# E-P-206-R1_0_Fuel_Cell_Control.net
KiCad netlist of a schematic drawn in EAGLE
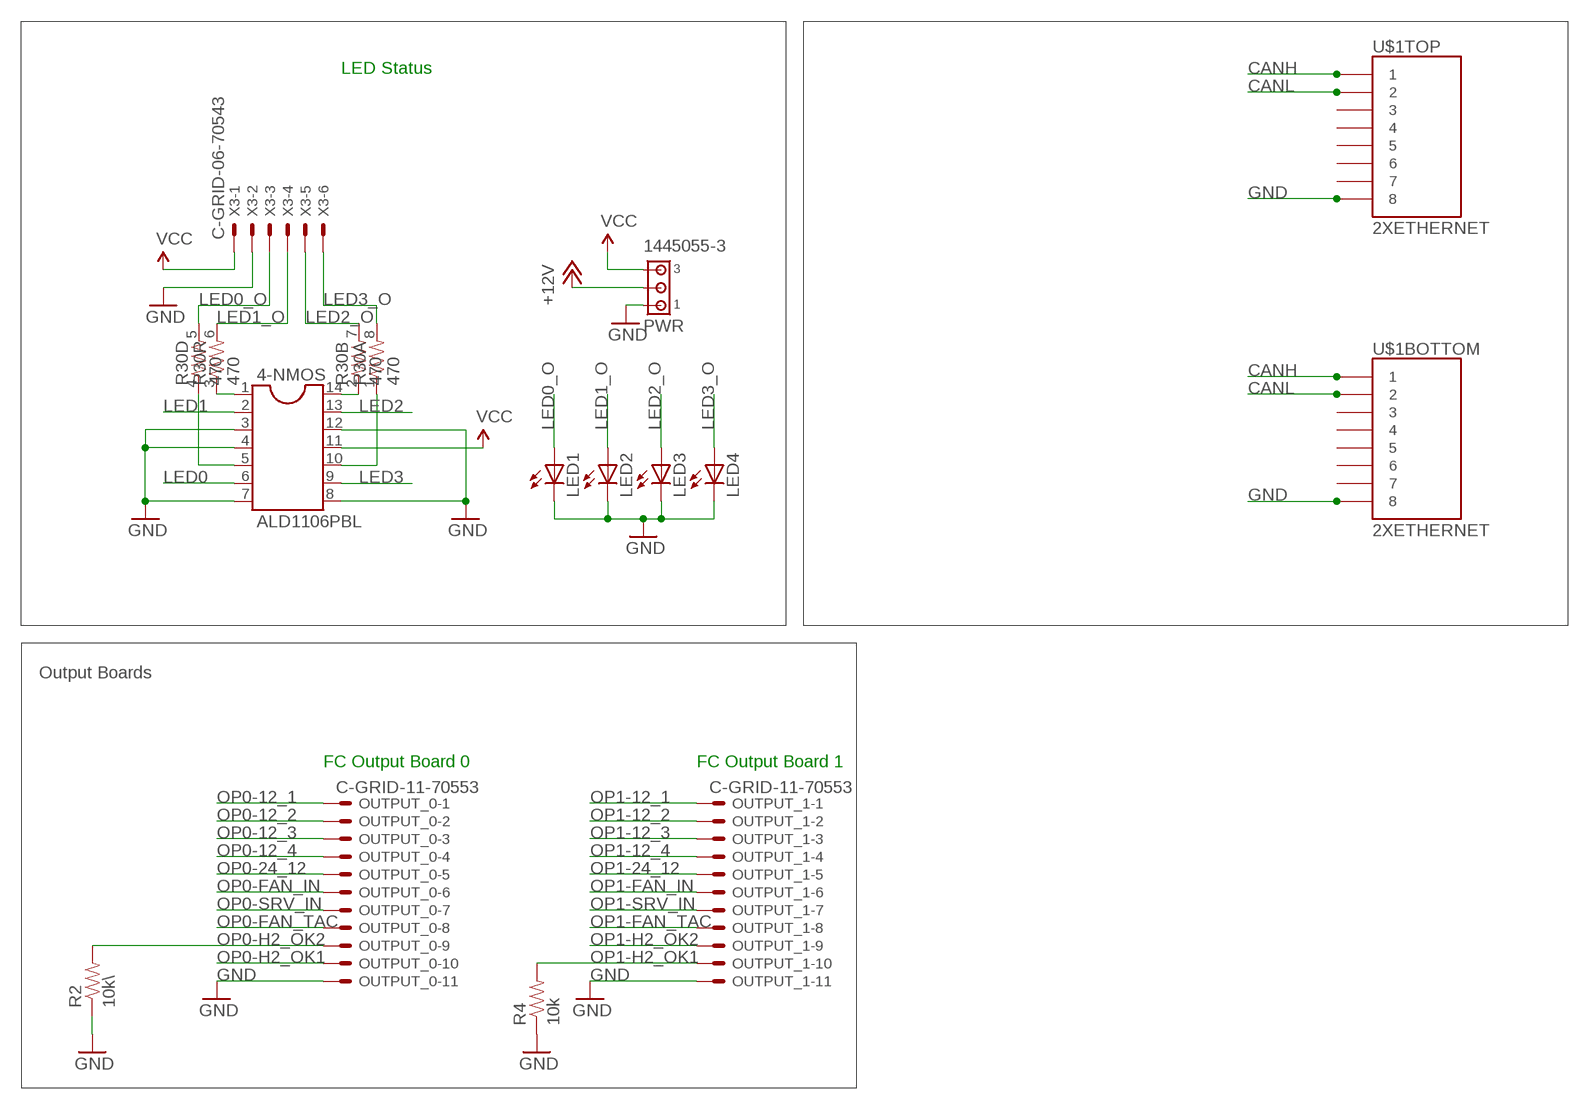
[diagram p0: schematic, sheet 1]
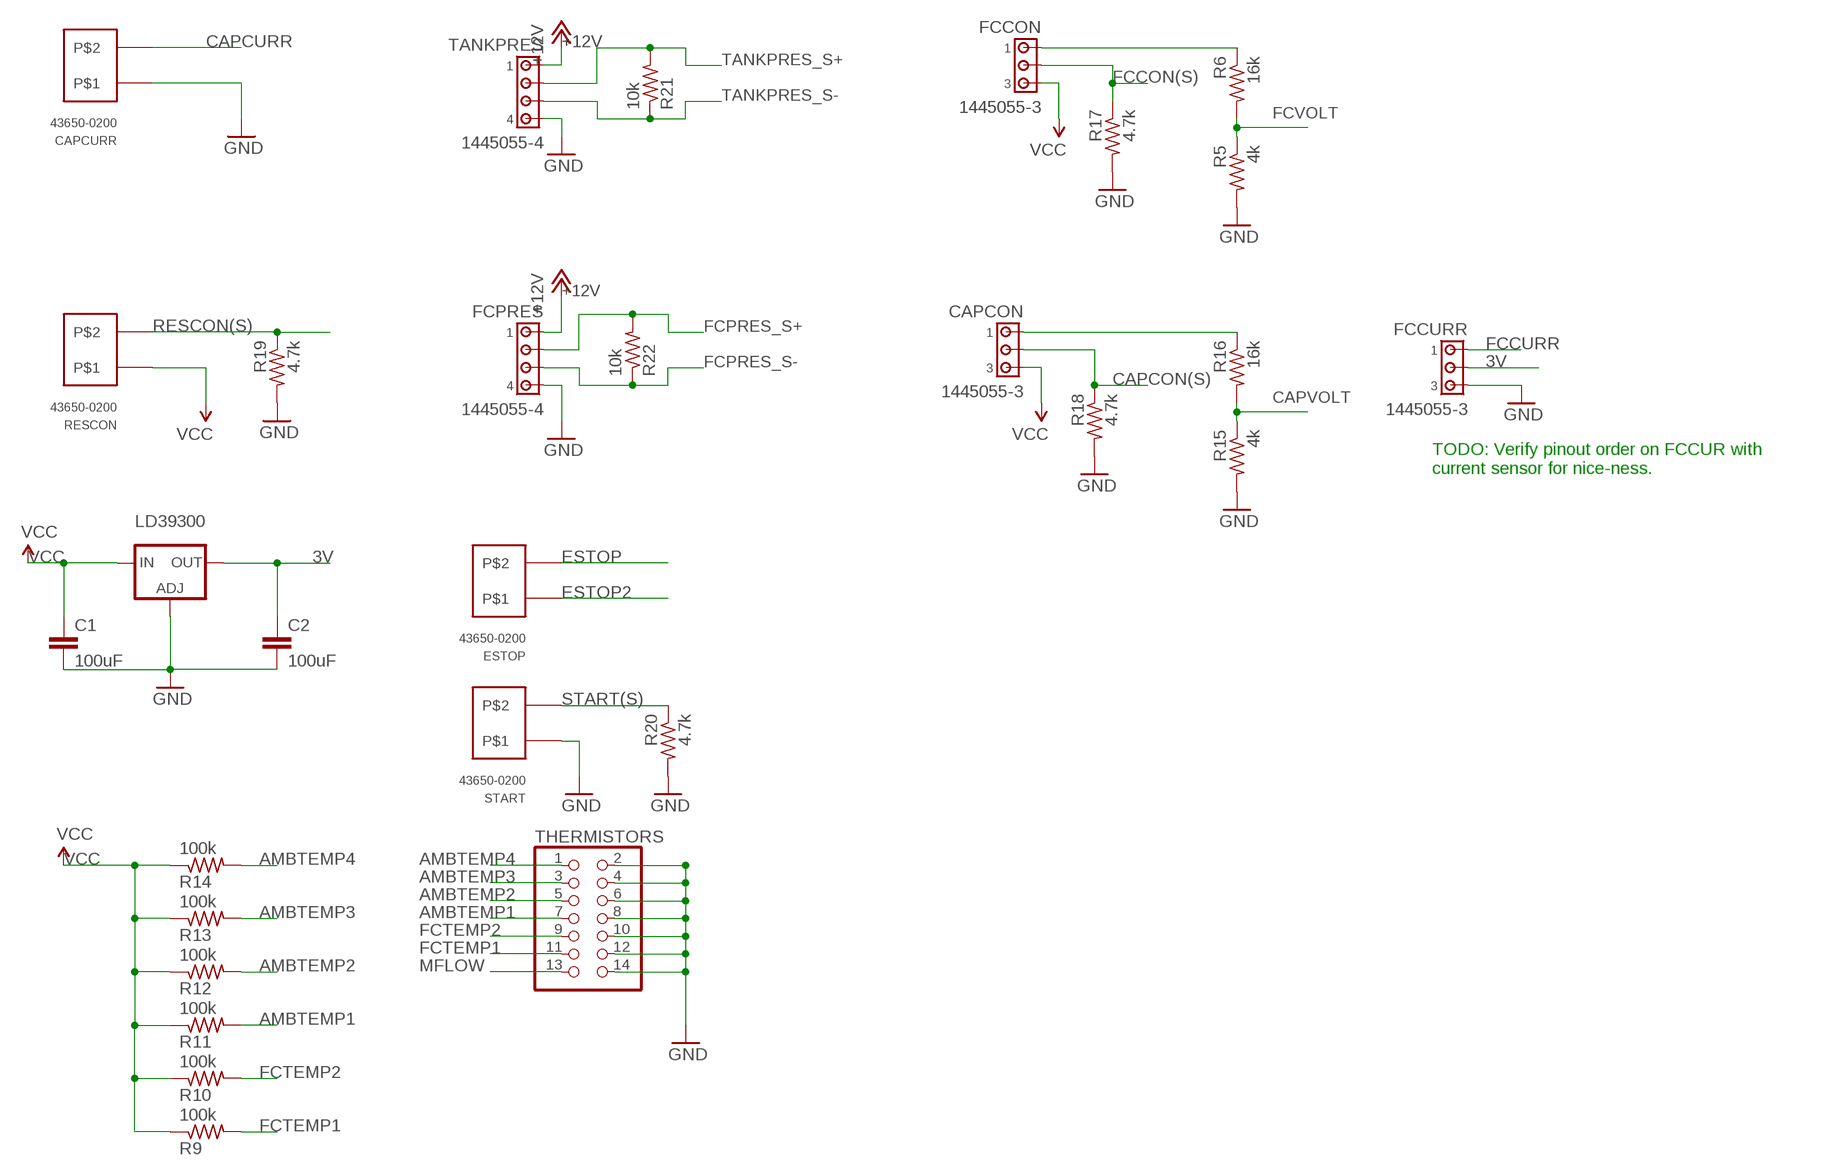
[diagram p1: schematic, sheet 2]
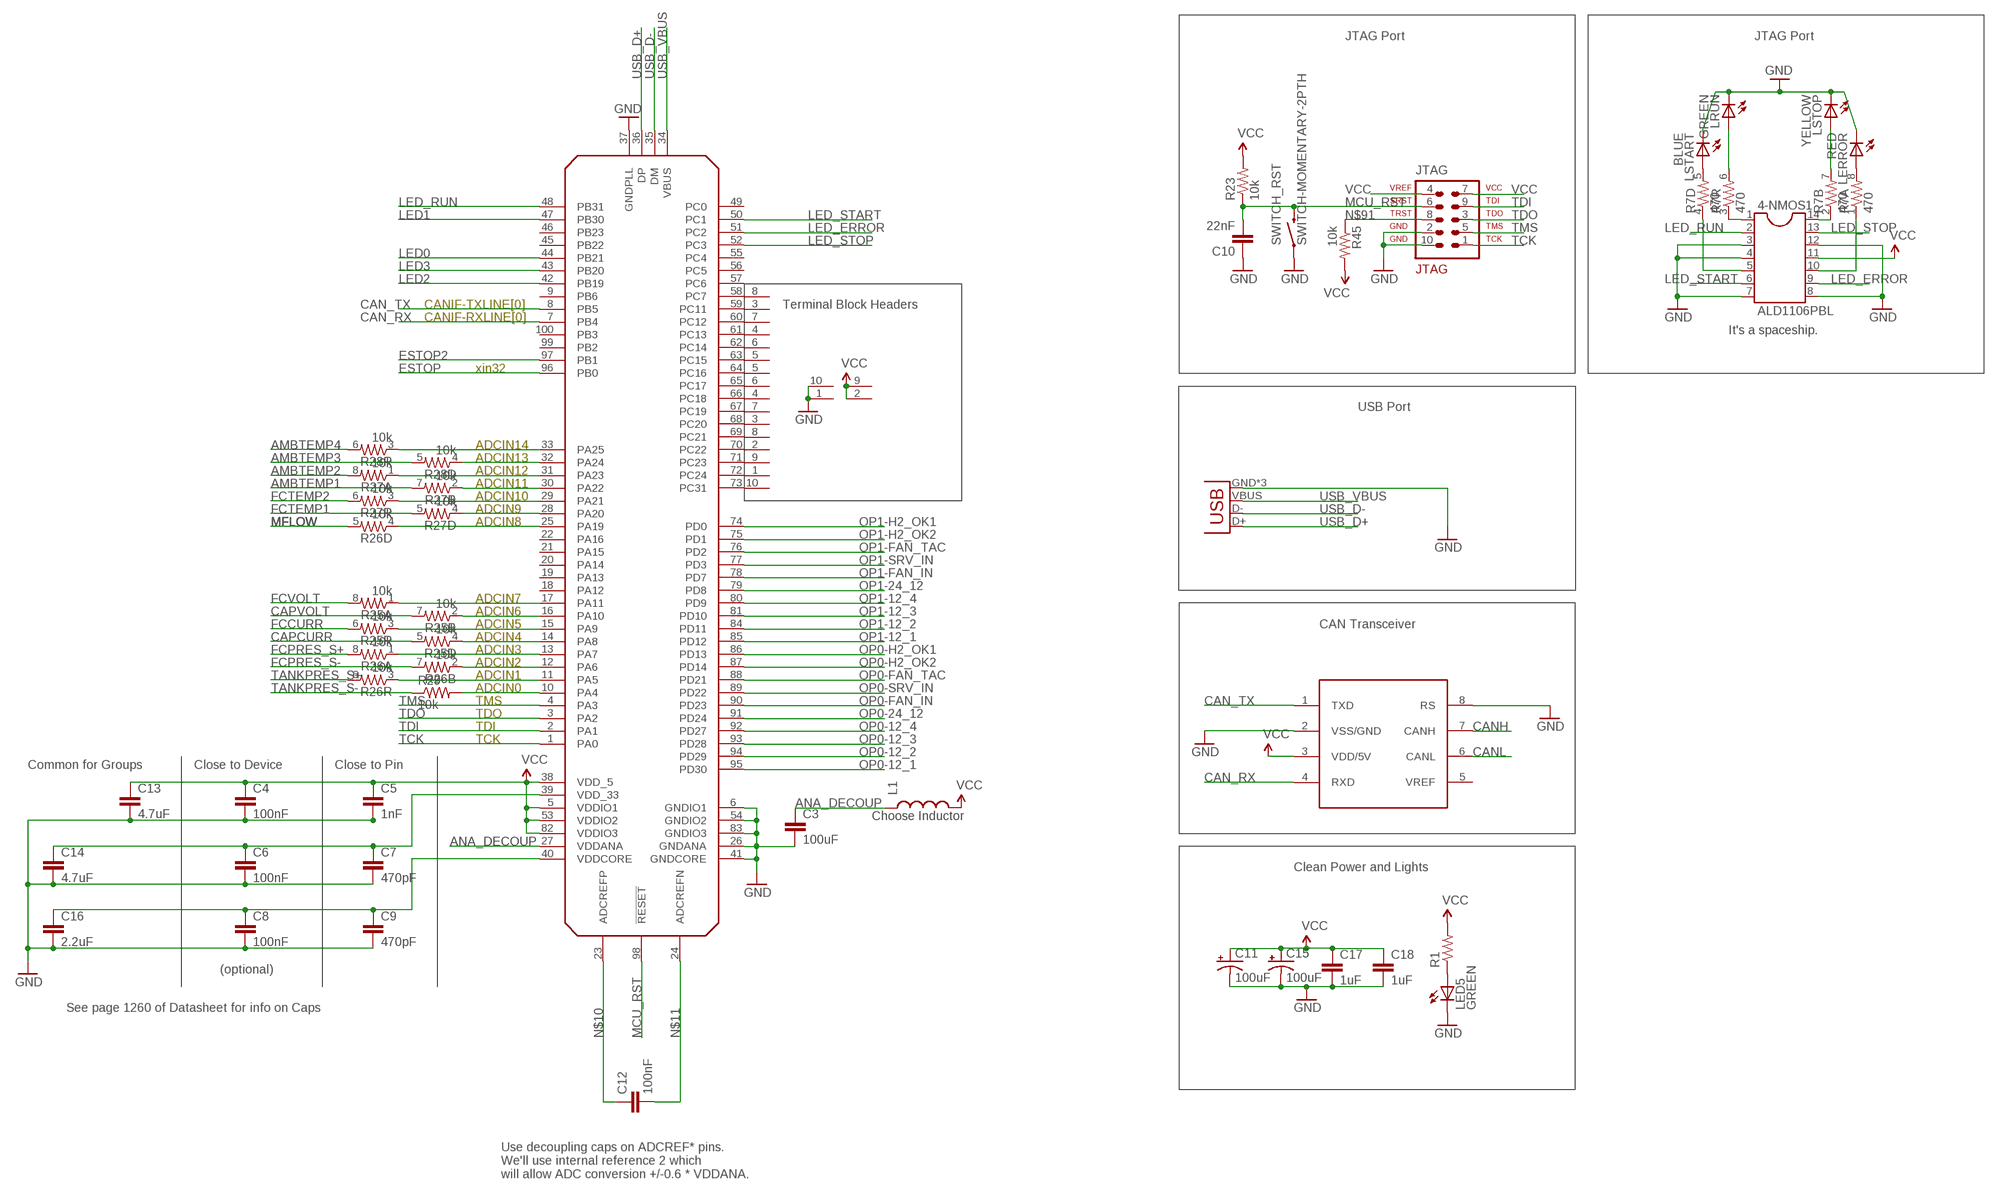
[diagram p2: schematic, sheet 3]

(export (version "E")
  (design (tool "Eeschema 10.0.6"))
  (components
    (comp (ref "C1")
      (value "100uF")
      (footprint "eagle-import:1206")
      (libsource (lib "eagle-import") (part "CAP1206"))
    )
    (comp (ref "C2")
      (value "100uF")
      (footprint "eagle-import:1206")
      (libsource (lib "eagle-import") (part "CAP1206"))
    )
    (comp (ref "CAPCON")
      (value "1445055-3")
      (footprint "eagle-import:1445055-3")
      (libsource (lib "eagle-import") (part "1445055-3"))
    )
    (comp (ref "CAPCURR")
      (value "43650-0200")
      (footprint "eagle-import:43650-0200")
      (libsource (lib "eagle-import") (part "43650-0200"))
    )
    (comp (ref "ESTOP")
      (value "43650-0200")
      (footprint "eagle-import:43650-0200")
      (libsource (lib "eagle-import") (part "43650-0200"))
    )
    (comp (ref "FCCON")
      (value "1445055-3")
      (footprint "eagle-import:1445055-3")
      (libsource (lib "eagle-import") (part "1445055-3"))
    )
    (comp (ref "FCCURR")
      (value "1445055-3")
      (footprint "eagle-import:1445055-3")
      (libsource (lib "eagle-import") (part "1445055-3"))
    )
    (comp (ref "FCPRES")
      (value "1445055-4")
      (footprint "eagle-import:1445055-4")
      (libsource (lib "eagle-import") (part "1445055-4"))
    )
    (comp (ref "LD39300")
      (value "LD117ADT50TR")
      (footprint "eagle-import:DPACK")
      (libsource (lib "eagle-import") (part "LD117A?DT50TR"))
    )
    (comp (ref "R5")
      (value "4k")
      (footprint "eagle-import:M0805")
      (libsource (lib "eagle-import") (part "R-US_M0805"))
    )
    (comp (ref "R6")
      (value "16k")
      (footprint "eagle-import:M0805")
      (libsource (lib "eagle-import") (part "R-US_M0805"))
    )
    (comp (ref "R9")
      (value "100k")
      (footprint "eagle-import:M0805")
      (libsource (lib "eagle-import") (part "R-US_M0805"))
    )
    (comp (ref "R10")
      (value "100k")
      (footprint "eagle-import:M0805")
      (libsource (lib "eagle-import") (part "R-US_M0805"))
    )
    (comp (ref "R11")
      (value "100k")
      (footprint "eagle-import:M0805")
      (libsource (lib "eagle-import") (part "R-US_M0805"))
    )
    (comp (ref "R12")
      (value "100k")
      (footprint "eagle-import:M0805")
      (libsource (lib "eagle-import") (part "R-US_M0805"))
    )
    (comp (ref "R13")
      (value "100k")
      (footprint "eagle-import:M0805")
      (libsource (lib "eagle-import") (part "R-US_M0805"))
    )
    (comp (ref "R14")
      (value "100k")
      (footprint "eagle-import:M0805")
      (libsource (lib "eagle-import") (part "R-US_M0805"))
    )
    (comp (ref "R15")
      (value "4k")
      (footprint "eagle-import:M0805")
      (libsource (lib "eagle-import") (part "R-US_M0805"))
    )
    (comp (ref "R16")
      (value "16k")
      (footprint "eagle-import:M0805")
      (libsource (lib "eagle-import") (part "R-US_M0805"))
    )
    (comp (ref "R17")
      (value "4.7k")
      (footprint "eagle-import:M0805")
      (libsource (lib "eagle-import") (part "R-US_M0805"))
    )
    (comp (ref "R18")
      (value "4.7k")
      (footprint "eagle-import:M0805")
      (libsource (lib "eagle-import") (part "R-US_M0805"))
    )
    (comp (ref "R19")
      (value "4.7k")
      (footprint "eagle-import:M0805")
      (libsource (lib "eagle-import") (part "R-US_M0805"))
    )
    (comp (ref "R20")
      (value "4.7k")
      (footprint "eagle-import:M0805")
      (libsource (lib "eagle-import") (part "R-US_M0805"))
    )
    (comp (ref "R21")
      (value "10k")
      (footprint "eagle-import:M0805")
      (libsource (lib "eagle-import") (part "R-US_M0805"))
    )
    (comp (ref "R22")
      (value "10k")
      (footprint "eagle-import:M0805")
      (libsource (lib "eagle-import") (part "R-US_M0805"))
    )
    (comp (ref "RESCON")
      (value "43650-0200")
      (footprint "eagle-import:43650-0200")
      (libsource (lib "eagle-import") (part "43650-0200"))
    )
    (comp (ref "START")
      (value "43650-0200")
      (footprint "eagle-import:43650-0200")
      (libsource (lib "eagle-import") (part "43650-0200"))
    )
    (comp (ref "TANKPRES")
      (value "1445055-4")
      (footprint "eagle-import:1445055-4")
      (libsource (lib "eagle-import") (part "1445055-4"))
    )
    (comp (ref "THERMISTORS")
      (value "PINHD-2X7")
      (footprint "eagle-import:2X07")
      (libsource (lib "eagle-import") (part "PINHD-2X7"))
    )
    (comp (ref "4-NMOS1")
      (value "ALD1106PBL")
      (footprint "eagle-import:SOIC-14")
      (libsource (lib "eagle-import") (part "DIL14SOIC"))
    )
    (comp (ref "C3")
      (value "100uF")
      (footprint "eagle-import:0805")
      (libsource (lib "eagle-import") (part "SparkFun-Capacitors_CAP0805"))
    )
    (comp (ref "C4")
      (value "100nF")
      (footprint "eagle-import:0805")
      (libsource (lib "eagle-import") (part "SparkFun-Capacitors_CAP0805"))
    )
    (comp (ref "C5")
      (value "1nF")
      (footprint "eagle-import:0805")
      (libsource (lib "eagle-import") (part "SparkFun-Capacitors_CAP0805"))
    )
    (comp (ref "C6")
      (value "100nF")
      (footprint "eagle-import:0805")
      (libsource (lib "eagle-import") (part "SparkFun-Capacitors_CAP0805"))
    )
    (comp (ref "C7")
      (value "470pF")
      (footprint "eagle-import:0805")
      (libsource (lib "eagle-import") (part "SparkFun-Capacitors_CAP0805"))
    )
    (comp (ref "C8")
      (value "100nF")
      (footprint "eagle-import:0805")
      (libsource (lib "eagle-import") (part "SparkFun-Capacitors_CAP0805"))
    )
    (comp (ref "C9")
      (value "470pF")
      (footprint "eagle-import:0805")
      (libsource (lib "eagle-import") (part "SparkFun-Capacitors_CAP0805"))
    )
    (comp (ref "C10")
      (value "22nF")
      (footprint "eagle-import:0805")
      (libsource (lib "eagle-import") (part "SparkFun-Capacitors_CAP0805"))
    )
    (comp (ref "C11")
      (value "100uF")
      (footprint "eagle-import:PANASONIC_C")
      (libsource (lib "eagle-import") (part "CAP_POLC"))
    )
    (comp (ref "C12")
      (value "100nF")
      (footprint "eagle-import:0805")
      (libsource (lib "eagle-import") (part "SparkFun-Capacitors_CAP0805"))
    )
    (comp (ref "C13")
      (value "4.7uF")
      (footprint "eagle-import:0805")
      (libsource (lib "eagle-import") (part "SparkFun-Capacitors_CAP0805"))
    )
    (comp (ref "C14")
      (value "4.7uF")
      (footprint "eagle-import:0805")
      (libsource (lib "eagle-import") (part "SparkFun-Capacitors_CAP0805"))
    )
    (comp (ref "C15")
      (value "100uF")
      (footprint "eagle-import:PANASONIC_C")
      (libsource (lib "eagle-import") (part "CAP_POLC"))
    )
    (comp (ref "C16")
      (value "2.2uF")
      (footprint "eagle-import:0805")
      (libsource (lib "eagle-import") (part "SparkFun-Capacitors_CAP0805"))
    )
    (comp (ref "C17")
      (value "1uF")
      (footprint "eagle-import:0805")
      (libsource (lib "eagle-import") (part "SparkFun-Capacitors_CAP0805"))
    )
    (comp (ref "C18")
      (value "1uF")
      (footprint "eagle-import:0805")
      (libsource (lib "eagle-import") (part "SparkFun-Capacitors_CAP0805"))
    )
    (comp (ref "JP2")
      (value "USB-MICROB")
      (footprint "eagle-import:USB-MICROB")
      (libsource (lib "eagle-import") (part "USB-MICROB"))
    )
    (comp (ref "JTAG")
      (value "AVR-JTAG-10")
      (footprint "eagle-import:AVR-JTAG-10")
      (libsource (lib "eagle-import") (part "AVR-JTAG-10"))
    )
    (comp (ref "L1")
      (value "INDUCTOR0805")
      (footprint "eagle-import:0805")
      (libsource (lib "eagle-import") (part "INDUCTOR0805"))
    )
    (comp (ref "LED5")
      (value "GREEN")
      (footprint "eagle-import:LED-1206")
      (libsource (lib "eagle-import") (part "LED1206"))
    )
    (comp (ref "LERROR")
      (value "RED")
      (footprint "eagle-import:CHIPLED_1206")
      (libsource (lib "eagle-import") (part "LEDCHIPLED_1206"))
    )
    (comp (ref "LRUN")
      (value "GREEN")
      (footprint "eagle-import:CHIPLED_1206")
      (libsource (lib "eagle-import") (part "LEDCHIPLED_1206"))
    )
    (comp (ref "LSTART")
      (value "BLUE")
      (footprint "eagle-import:CHIPLED_1206")
      (libsource (lib "eagle-import") (part "LEDCHIPLED_1206"))
    )
    (comp (ref "LSTOP")
      (value "YELLOW")
      (footprint "eagle-import:CHIPLED_1206")
      (libsource (lib "eagle-import") (part "LEDCHIPLED_1206"))
    )
    (comp (ref "MCU")
      (value "AT32UC3C1512")
      (footprint "eagle-import:TQFP100")
      (libsource (lib "eagle-import") (part "AT32UC3C1512"))
    )
    (comp (ref "R1")
      (value "RESISTOR0805-RES")
      (footprint "eagle-import:0805")
      (libsource (lib "eagle-import") (part "SparkFun-Passives_RESISTOR0805-RES"))
    )
    (comp (ref "R7")
      (value "470")
      (footprint "eagle-import:0603-ARV")
      (libsource (lib "eagle-import") (part "RESISTOR-ARRAY0603-ARV"))
    )
    (comp (ref "R23")
      (value "10k")
      (footprint "eagle-import:0805")
      (libsource (lib "eagle-import") (part "SparkFun-Resistors_RESISTOR0805-RES"))
    )
    (comp (ref "R25")
      (value "10k")
      (footprint "eagle-import:0603-ARV")
      (libsource (lib "eagle-import") (part "RESISTOR-ARRAY0603-ARV"))
    )
    (comp (ref "R26")
      (value "10k")
      (footprint "eagle-import:0603-ARV")
      (libsource (lib "eagle-import") (part "RESISTOR-ARRAY0603-ARV"))
    )
    (comp (ref "R27")
      (value "10k")
      (footprint "eagle-import:0603-ARV")
      (libsource (lib "eagle-import") (part "RESISTOR-ARRAY0603-ARV"))
    )
    (comp (ref "R28")
      (value "10k")
      (footprint "eagle-import:0603-ARV")
      (libsource (lib "eagle-import") (part "RESISTOR-ARRAY0603-ARV"))
    )
    (comp (ref "R29")
      (value "10k")
      (footprint "eagle-import:0805")
      (libsource (lib "eagle-import") (part "SparkFun-Resistors_RESISTOR0805-RES"))
    )
    (comp (ref "R45")
      (value "10k")
      (footprint "eagle-import:0805")
      (libsource (lib "eagle-import") (part "SparkFun-Resistors_RESISTOR0805-RES"))
    )
    (comp (ref "SWITCH_RST")
      (value "SWITCH-MOMENTARY-2PTH")
      (footprint "eagle-import:TACTILE-PTH")
      (libsource (lib "eagle-import") (part "SWITCH-MOMENTARY-2PTH"))
    )
    (comp (ref "U$2")
      (value "10X1PCBBLOCK")
      (footprint "eagle-import:10X1PCBBLOCK")
      (libsource (lib "eagle-import") (part "10X1PCBBLOCK"))
    )
    (comp (ref "U$3")
      (value "10X1PCBBLOCK")
      (footprint "eagle-import:10X1PCBBLOCK")
      (libsource (lib "eagle-import") (part "10X1PCBBLOCK"))
    )
    (comp (ref "U$4")
      (value "MCP2551")
      (footprint "eagle-import:DIP8")
      (libsource (lib "eagle-import") (part "MCP2551"))
    )
    (comp (ref "4-NMOS")
      (value "ALD1106PBL")
      (footprint "eagle-import:SOIC-14")
      (libsource (lib "eagle-import") (part "DIL14SOIC"))
    )
    (comp (ref "LED1")
      (value "LEDCHIPLED_1206")
      (footprint "eagle-import:CHIPLED_1206")
      (libsource (lib "eagle-import") (part "LEDCHIPLED_1206"))
    )
    (comp (ref "LED2")
      (value "LEDCHIPLED_1206")
      (footprint "eagle-import:CHIPLED_1206")
      (libsource (lib "eagle-import") (part "LEDCHIPLED_1206"))
    )
    (comp (ref "LED3")
      (value "LEDCHIPLED_1206")
      (footprint "eagle-import:CHIPLED_1206")
      (libsource (lib "eagle-import") (part "LEDCHIPLED_1206"))
    )
    (comp (ref "LED4")
      (value "LEDCHIPLED_1206")
      (footprint "eagle-import:CHIPLED_1206")
      (libsource (lib "eagle-import") (part "LEDCHIPLED_1206"))
    )
    (comp (ref "OUTPUT_0")
      (value "C-GRID-11-70553")
      (footprint "eagle-import:70553-11")
      (libsource (lib "eagle-import") (part "C-GRID-11-70553"))
    )
    (comp (ref "OUTPUT_1")
      (value "C-GRID-11-70553")
      (footprint "eagle-import:70553-11")
      (libsource (lib "eagle-import") (part "C-GRID-11-70553"))
    )
    (comp (ref "PWR")
      (value "1445055-3")
      (footprint "eagle-import:1445055-3")
      (libsource (lib "eagle-import") (part "1445055-3"))
    )
    (comp (ref "R2")
      (value "10k\\")
      (footprint "eagle-import:1206")
      (libsource (lib "eagle-import") (part "RESISTOR1206"))
    )
    (comp (ref "R4")
      (value "10k")
      (footprint "eagle-import:1206")
      (libsource (lib "eagle-import") (part "RESISTOR1206"))
    )
    (comp (ref "R30")
      (value "470")
      (footprint "eagle-import:0603-ARV")
      (libsource (lib "eagle-import") (part "RESISTOR-ARRAY0603-ARV"))
    )
    (comp (ref "U$1")
      (value "2XETHERNET")
      (footprint "eagle-import:2XETHERNET")
      (libsource (lib "eagle-import") (part "2XETHERNET"))
    )
    (comp (ref "X3")
      (value "C-GRID-06-70543")
      (footprint "eagle-import:70543-06")
      (libsource (lib "eagle-import") (part "C-GRID-06-70543"))
    )
  )
  (nets
    (net (code "1") (name "+12V") (class "Default")
      (node (ref "FCPRES") (pin "1") (pinfunction "1_1") (pintype "passive"))
      (node (ref "PWR") (pin "2") (pinfunction "2_2") (pintype "passive"))
      (node (ref "TANKPRES") (pin "1") (pinfunction "1_1") (pintype "passive"))
    )
    (net (code "2") (name "3V") (class "Default")
      (node (ref "C2") (pin "1") (pinfunction "1_1") (pintype "passive"))
      (node (ref "FCCURR") (pin "2") (pinfunction "2_2") (pintype "passive"))
      (node (ref "LD39300") (pin "4") (pinfunction "OUT_4") (pintype "passive"))
    )
    (net (code "3") (name "AMBTEMP1") (class "Default")
      (node (ref "R11") (pin "2") (pinfunction "2_2") (pintype "passive"))
      (node (ref "R27") (pin "7") (pinfunction "2_7") (pintype "passive"))
      (node (ref "THERMISTORS") (pin "7") (pinfunction "7_7") (pintype "passive"))
    )
    (net (code "4") (name "AMBTEMP2") (class "Default")
      (node (ref "R12") (pin "2") (pinfunction "2_2") (pintype "passive"))
      (node (ref "R27") (pin "8") (pinfunction "2_8") (pintype "passive"))
      (node (ref "THERMISTORS") (pin "5") (pinfunction "5_5") (pintype "passive"))
    )
    (net (code "5") (name "AMBTEMP3") (class "Default")
      (node (ref "R13") (pin "2") (pinfunction "2_2") (pintype "passive"))
      (node (ref "R28") (pin "5") (pinfunction "2_5") (pintype "passive"))
      (node (ref "THERMISTORS") (pin "3") (pinfunction "3_3") (pintype "passive"))
    )
    (net (code "6") (name "AMBTEMP4") (class "Default")
      (node (ref "R14") (pin "2") (pinfunction "2_2") (pintype "passive"))
      (node (ref "R28") (pin "6") (pinfunction "2_6") (pintype "passive"))
      (node (ref "THERMISTORS") (pin "1") (pinfunction "1_1") (pintype "passive"))
    )
    (net (code "7") (name "ANA_DECOUP") (class "Default")
      (node (ref "C3") (pin "1") (pinfunction "1_1") (pintype "passive"))
      (node (ref "L1") (pin "1") (pinfunction "1_1") (pintype "passive"))
      (node (ref "MCU") (pin "27") (pinfunction "VDDANA_27") (pintype "bidirectional"))
    )
    (net (code "8") (name "CANH") (class "Default")
      (node (ref "U$1") (pin "B_1") (pinfunction "1_B_1") (pintype "bidirectional"))
      (node (ref "U$1") (pin "T_1") (pinfunction "1_T_1") (pintype "bidirectional"))
      (node (ref "U$4") (pin "7") (pinfunction "CANH_7") (pintype "bidirectional"))
    )
    (net (code "9") (name "CANL") (class "Default")
      (node (ref "U$1") (pin "B_2") (pinfunction "2_B_2") (pintype "bidirectional"))
      (node (ref "U$1") (pin "T_2") (pinfunction "2_T_2") (pintype "bidirectional"))
      (node (ref "U$4") (pin "6") (pinfunction "CANL_6") (pintype "bidirectional"))
    )
    (net (code "10") (name "CAN_RX") (class "Default")
      (node (ref "MCU") (pin "7") (pinfunction "PB4_7") (pintype "bidirectional"))
      (node (ref "U$4") (pin "4") (pinfunction "RXD_4") (pintype "bidirectional"))
    )
    (net (code "11") (name "CAN_TX") (class "Default")
      (node (ref "MCU") (pin "8") (pinfunction "PB5_8") (pintype "bidirectional"))
      (node (ref "U$4") (pin "1") (pinfunction "TXD_1") (pintype "bidirectional"))
    )
    (net (code "12") (name "CAPCON(S)") (class "Default")
      (node (ref "CAPCON") (pin "2") (pinfunction "2_2") (pintype "passive"))
      (node (ref "R18") (pin "1") (pinfunction "1_1") (pintype "passive"))
    )
    (net (code "13") (name "CAPCURR") (class "Default")
      (node (ref "CAPCURR") (pin "P$1") (pinfunction "P$2_P$1") (pintype "bidirectional"))
      (node (ref "R25") (pin "5") (pinfunction "2_5") (pintype "passive"))
    )
    (net (code "14") (name "CAPVOLT") (class "Default")
      (node (ref "R15") (pin "1") (pinfunction "1_1") (pintype "passive"))
      (node (ref "R16") (pin "2") (pinfunction "2_2") (pintype "passive"))
      (node (ref "R25") (pin "7") (pinfunction "2_7") (pintype "passive"))
    )
    (net (code "15") (name "ESTOP") (class "Default")
      (node (ref "ESTOP") (pin "P$1") (pinfunction "P$2_P$1") (pintype "bidirectional"))
      (node (ref "MCU") (pin "96") (pinfunction "PB0_96") (pintype "bidirectional"))
    )
    (net (code "16") (name "ESTOP2") (class "Default")
      (node (ref "ESTOP") (pin "P$2") (pinfunction "P$1_P$2") (pintype "bidirectional"))
      (node (ref "MCU") (pin "97") (pinfunction "PB1_97") (pintype "bidirectional"))
    )
    (net (code "17") (name "FCCON(S)") (class "Default")
      (node (ref "FCCON") (pin "2") (pinfunction "2_2") (pintype "passive"))
      (node (ref "R17") (pin "1") (pinfunction "1_1") (pintype "passive"))
    )
    (net (code "18") (name "FCCURR") (class "Default")
      (node (ref "FCCURR") (pin "1") (pinfunction "1_1") (pintype "passive"))
      (node (ref "R25") (pin "6") (pinfunction "2_6") (pintype "passive"))
    )
    (net (code "19") (name "FCPRES_S+") (class "Default")
      (node (ref "FCPRES") (pin "2") (pinfunction "2_2") (pintype "passive"))
      (node (ref "R22") (pin "2") (pinfunction "2_2") (pintype "passive"))
      (node (ref "R26") (pin "8") (pinfunction "2_8") (pintype "passive"))
    )
    (net (code "20") (name "FCPRES_S-") (class "Default")
      (node (ref "FCPRES") (pin "3") (pinfunction "3_3") (pintype "passive"))
      (node (ref "R22") (pin "1") (pinfunction "1_1") (pintype "passive"))
      (node (ref "R26") (pin "7") (pinfunction "2_7") (pintype "passive"))
    )
    (net (code "21") (name "FCTEMP1") (class "Default")
      (node (ref "R27") (pin "5") (pinfunction "2_5") (pintype "passive"))
      (node (ref "R9") (pin "2") (pinfunction "2_2") (pintype "passive"))
      (node (ref "THERMISTORS") (pin "11") (pinfunction "11_11") (pintype "passive"))
    )
    (net (code "22") (name "FCTEMP2") (class "Default")
      (node (ref "R10") (pin "2") (pinfunction "2_2") (pintype "passive"))
      (node (ref "R27") (pin "6") (pinfunction "2_6") (pintype "passive"))
      (node (ref "THERMISTORS") (pin "9") (pinfunction "9_9") (pintype "passive"))
    )
    (net (code "23") (name "FCVOLT") (class "Default")
      (node (ref "R25") (pin "8") (pinfunction "2_8") (pintype "passive"))
      (node (ref "R5") (pin "1") (pinfunction "1_1") (pintype "passive"))
      (node (ref "R6") (pin "2") (pinfunction "2_2") (pintype "passive"))
    )
    (net (code "24") (name "GND") (class "Default")
      (node (ref "4-NMOS") (pin "12") (pinfunction "12_12") (pintype "passive"))
      (node (ref "4-NMOS") (pin "3") (pinfunction "3_3") (pintype "passive"))
      (node (ref "4-NMOS") (pin "4") (pinfunction "4_4") (pintype "passive"))
      (node (ref "4-NMOS") (pin "7") (pinfunction "7_7") (pintype "passive"))
      (node (ref "4-NMOS") (pin "8") (pinfunction "8_8") (pintype "passive"))
      (node (ref "4-NMOS1") (pin "12") (pinfunction "12_12") (pintype "passive"))
      (node (ref "4-NMOS1") (pin "3") (pinfunction "3_3") (pintype "passive"))
      (node (ref "4-NMOS1") (pin "4") (pinfunction "4_4") (pintype "passive"))
      (node (ref "4-NMOS1") (pin "7") (pinfunction "7_7") (pintype "passive"))
      (node (ref "4-NMOS1") (pin "8") (pinfunction "8_8") (pintype "passive"))
      (node (ref "C1") (pin "2") (pinfunction "2_2") (pintype "passive"))
      (node (ref "C10") (pin "1") (pinfunction "1_1") (pintype "passive"))
      (node (ref "C11") (pin "-") (pinfunction "-_-") (pintype "passive"))
      (node (ref "C13") (pin "2") (pinfunction "2_2") (pintype "passive"))
      (node (ref "C14") (pin "2") (pinfunction "2_2") (pintype "passive"))
      (node (ref "C15") (pin "-") (pinfunction "-_-") (pintype "passive"))
      (node (ref "C16") (pin "2") (pinfunction "2_2") (pintype "passive"))
      (node (ref "C17") (pin "2") (pinfunction "2_2") (pintype "passive"))
      (node (ref "C18") (pin "2") (pinfunction "2_2") (pintype "passive"))
      (node (ref "C2") (pin "2") (pinfunction "2_2") (pintype "passive"))
      (node (ref "C3") (pin "2") (pinfunction "2_2") (pintype "passive"))
      (node (ref "C4") (pin "2") (pinfunction "2_2") (pintype "passive"))
      (node (ref "C5") (pin "2") (pinfunction "2_2") (pintype "passive"))
      (node (ref "C6") (pin "2") (pinfunction "2_2") (pintype "passive"))
      (node (ref "C7") (pin "2") (pinfunction "2_2") (pintype "passive"))
      (node (ref "C8") (pin "2") (pinfunction "2_2") (pintype "passive"))
      (node (ref "C9") (pin "2") (pinfunction "2_2") (pintype "passive"))
      (node (ref "CAPCURR") (pin "P$2") (pinfunction "P$1_P$2") (pintype "bidirectional"))
      (node (ref "FCCURR") (pin "3") (pinfunction "3_3") (pintype "passive"))
      (node (ref "FCPRES") (pin "4") (pinfunction "4_4") (pintype "passive"))
      (node (ref "JP2") (pin "GND") (pinfunction "GND_GND") (pintype "bidirectional"))
      (node (ref "JP2") (pin "MT1") (pinfunction "GND_MT1") (pintype "bidirectional"))
      (node (ref "JP2") (pin "MT2") (pinfunction "GND_MT2") (pintype "bidirectional"))
      (node (ref "JTAG") (pin "10") (pinfunction "10_10") (pintype "passive"))
      (node (ref "JTAG") (pin "2") (pinfunction "2_2") (pintype "passive"))
      (node (ref "LD39300") (pin "1") (pinfunction "ADJ_1") (pintype "input"))
      (node (ref "LED1") (pin "C") (pinfunction "C_C") (pintype "passive"))
      (node (ref "LED2") (pin "C") (pinfunction "C_C") (pintype "passive"))
      (node (ref "LED3") (pin "C") (pinfunction "C_C") (pintype "passive"))
      (node (ref "LED4") (pin "C") (pinfunction "C_C") (pintype "passive"))
      (node (ref "LED5") (pin "C") (pinfunction "C_C") (pintype "passive"))
      (node (ref "LERROR") (pin "C") (pinfunction "C_C") (pintype "passive"))
      (node (ref "LRUN") (pin "C") (pinfunction "C_C") (pintype "passive"))
      (node (ref "LSTART") (pin "C") (pinfunction "C_C") (pintype "passive"))
      (node (ref "LSTOP") (pin "C") (pinfunction "C_C") (pintype "passive"))
      (node (ref "MCU") (pin "26") (pinfunction "GNDANA_26") (pintype "bidirectional"))
      (node (ref "MCU") (pin "37") (pinfunction "GNDPLL_37") (pintype "bidirectional"))
      (node (ref "MCU") (pin "41") (pinfunction "GNDCORE_41") (pintype "bidirectional"))
      (node (ref "MCU") (pin "54") (pinfunction "GNDIO2_54") (pintype "bidirectional"))
      (node (ref "MCU") (pin "6") (pinfunction "GNDIO1_6") (pintype "bidirectional"))
      (node (ref "MCU") (pin "83") (pinfunction "GNDIO3_83") (pintype "bidirectional"))
      (node (ref "OUTPUT_0") (pin "11") (pinfunction "S_11") (pintype "passive"))
      (node (ref "OUTPUT_1") (pin "11") (pinfunction "S_11") (pintype "passive"))
      (node (ref "PWR") (pin "1") (pinfunction "1_1") (pintype "passive"))
      (node (ref "R15") (pin "2") (pinfunction "2_2") (pintype "passive"))
      (node (ref "R17") (pin "2") (pinfunction "2_2") (pintype "passive"))
      (node (ref "R18") (pin "2") (pinfunction "2_2") (pintype "passive"))
      (node (ref "R19") (pin "2") (pinfunction "2_2") (pintype "passive"))
      (node (ref "R2") (pin "1") (pinfunction "1_1") (pintype "passive"))
      (node (ref "R20") (pin "2") (pinfunction "2_2") (pintype "passive"))
      (node (ref "R4") (pin "1") (pinfunction "1_1") (pintype "passive"))
      (node (ref "R5") (pin "2") (pinfunction "2_2") (pintype "passive"))
      (node (ref "START") (pin "P$2") (pinfunction "P$1_P$2") (pintype "bidirectional"))
      (node (ref "SWITCH_RST") (pin "1") (pinfunction "1_1") (pintype "passive"))
      (node (ref "TANKPRES") (pin "4") (pinfunction "4_4") (pintype "passive"))
      (node (ref "THERMISTORS") (pin "10") (pinfunction "10_10") (pintype "passive"))
      (node (ref "THERMISTORS") (pin "12") (pinfunction "12_12") (pintype "passive"))
      (node (ref "THERMISTORS") (pin "14") (pinfunction "14_14") (pintype "passive"))
      (node (ref "THERMISTORS") (pin "2") (pinfunction "2_2") (pintype "passive"))
      (node (ref "THERMISTORS") (pin "4") (pinfunction "4_4") (pintype "passive"))
      (node (ref "THERMISTORS") (pin "6") (pinfunction "6_6") (pintype "passive"))
      (node (ref "THERMISTORS") (pin "8") (pinfunction "8_8") (pintype "passive"))
      (node (ref "U$1") (pin "B_8") (pinfunction "8_B_8") (pintype "bidirectional"))
      (node (ref "U$1") (pin "T_8") (pinfunction "8_T_8") (pintype "bidirectional"))
      (node (ref "U$2") (pin "10") (pinfunction "P$1_10") (pintype "bidirectional"))
      (node (ref "U$3") (pin "1") (pinfunction "P$1_1") (pintype "bidirectional"))
      (node (ref "U$4") (pin "2") (pinfunction "VSS/GND_2") (pintype "bidirectional"))
      (node (ref "U$4") (pin "8") (pinfunction "RS_8") (pintype "bidirectional"))
      (node (ref "X3") (pin "2") (pinfunction "S_2") (pintype "passive"))
    )
    (net (code "25") (name "LED0") (class "Default")
      (node (ref "4-NMOS") (pin "6") (pinfunction "6_6") (pintype "passive"))
      (node (ref "MCU") (pin "44") (pinfunction "PB21_44") (pintype "bidirectional"))
    )
    (net (code "26") (name "LED0_O") (class "Default")
      (node (ref "LED1") (pin "A") (pinfunction "A_A") (pintype "passive"))
      (node (ref "R30") (pin "5") (pinfunction "2_5") (pintype "passive"))
      (node (ref "X3") (pin "3") (pinfunction "S_3") (pintype "passive"))
    )
    (net (code "27") (name "LED1") (class "Default")
      (node (ref "4-NMOS") (pin "2") (pinfunction "2_2") (pintype "passive"))
      (node (ref "MCU") (pin "47") (pinfunction "PB30_47") (pintype "bidirectional"))
    )
    (net (code "28") (name "LED1_O") (class "Default")
      (node (ref "LED2") (pin "A") (pinfunction "A_A") (pintype "passive"))
      (node (ref "R30") (pin "6") (pinfunction "2_6") (pintype "passive"))
      (node (ref "X3") (pin "4") (pinfunction "S_4") (pintype "passive"))
    )
    (net (code "29") (name "LED2") (class "Default")
      (node (ref "4-NMOS") (pin "13") (pinfunction "13_13") (pintype "passive"))
      (node (ref "MCU") (pin "42") (pinfunction "PB19_42") (pintype "bidirectional"))
    )
    (net (code "30") (name "LED2_O") (class "Default")
      (node (ref "LED3") (pin "A") (pinfunction "A_A") (pintype "passive"))
      (node (ref "R30") (pin "7") (pinfunction "2_7") (pintype "passive"))
      (node (ref "X3") (pin "5") (pinfunction "S_5") (pintype "passive"))
    )
    (net (code "31") (name "LED3") (class "Default")
      (node (ref "4-NMOS") (pin "9") (pinfunction "9_9") (pintype "passive"))
      (node (ref "MCU") (pin "43") (pinfunction "PB20_43") (pintype "bidirectional"))
    )
    (net (code "32") (name "LED3_O") (class "Default")
      (node (ref "LED4") (pin "A") (pinfunction "A_A") (pintype "passive"))
      (node (ref "R30") (pin "8") (pinfunction "2_8") (pintype "passive"))
      (node (ref "X3") (pin "6") (pinfunction "S_6") (pintype "passive"))
    )
    (net (code "33") (name "LED_ERROR") (class "Default")
      (node (ref "4-NMOS1") (pin "9") (pinfunction "9_9") (pintype "passive"))
      (node (ref "MCU") (pin "51") (pinfunction "PC2_51") (pintype "bidirectional"))
    )
    (net (code "34") (name "LED_RUN") (class "Default")
      (node (ref "4-NMOS1") (pin "2") (pinfunction "2_2") (pintype "passive"))
      (node (ref "MCU") (pin "48") (pinfunction "PB31_48") (pintype "bidirectional"))
    )
    (net (code "35") (name "LED_START") (class "Default")
      (node (ref "4-NMOS1") (pin "6") (pinfunction "6_6") (pintype "passive"))
      (node (ref "MCU") (pin "50") (pinfunction "PC1_50") (pintype "bidirectional"))
    )
    (net (code "36") (name "LED_STOP") (class "Default")
      (node (ref "4-NMOS1") (pin "13") (pinfunction "13_13") (pintype "passive"))
      (node (ref "MCU") (pin "52") (pinfunction "PC3_52") (pintype "bidirectional"))
    )
    (net (code "37") (name "MCU_RST") (class "Default")
      (node (ref "C10") (pin "2") (pinfunction "2_2") (pintype "passive"))
      (node (ref "JTAG") (pin "6") (pinfunction "6_6") (pintype "passive"))
      (node (ref "MCU") (pin "98") (pinfunction "~{RESET}_98") (pintype "bidirectional"))
      (node (ref "R23") (pin "1") (pinfunction "1_1") (pintype "passive"))
      (node (ref "SWITCH_RST") (pin "3") (pinfunction "2_3") (pintype "passive"))
    )
    (net (code "38") (name "MFLOW") (class "Default")
      (node (ref "R26") (pin "5") (pinfunction "2_5") (pintype "passive"))
      (node (ref "THERMISTORS") (pin "13") (pinfunction "13_13") (pintype "passive"))
    )
    (net (code "39") (name "N$10") (class "Default")
      (node (ref "C12") (pin "1") (pinfunction "1_1") (pintype "passive"))
      (node (ref "MCU") (pin "23") (pinfunction "ADCREFP_23") (pintype "bidirectional"))
    )
    (net (code "40") (name "N$11") (class "Default")
      (node (ref "C12") (pin "2") (pinfunction "2_2") (pintype "passive"))
      (node (ref "MCU") (pin "24") (pinfunction "ADCREFN_24") (pintype "bidirectional"))
    )
    (net (code "41") (name "N$91") (class "Default")
      (node (ref "JTAG") (pin "8") (pinfunction "8_8") (pintype "passive"))
      (node (ref "R45") (pin "1") (pinfunction "1_1") (pintype "passive"))
    )
    (net (code "42") (name "Net-(4-NMOS-Pad10)") (class "Default")
      (node (ref "4-NMOS") (pin "10") (pinfunction "10_10") (pintype "passive"))
      (node (ref "R30") (pin "1") (pinfunction "1_1") (pintype "passive"))
    )
    (net (code "43") (name "Net-(4-NMOS1-Pad10)") (class "Default")
      (node (ref "4-NMOS1") (pin "10") (pinfunction "10_10") (pintype "passive"))
      (node (ref "R7") (pin "1") (pinfunction "1_1") (pintype "passive"))
    )
    (net (code "44") (name "Net-(CAPCON-Pad1)") (class "Default")
      (node (ref "CAPCON") (pin "1") (pinfunction "1_1") (pintype "passive"))
      (node (ref "R16") (pin "1") (pinfunction "1_1") (pintype "passive"))
    )
    (net (code "45") (name "Net-(FCCON-Pad1)") (class "Default")
      (node (ref "FCCON") (pin "1") (pinfunction "1_1") (pintype "passive"))
      (node (ref "R6") (pin "1") (pinfunction "1_1") (pintype "passive"))
    )
    (net (code "46") (name "Net-(LED5-PadA)") (class "Default")
      (node (ref "LED5") (pin "A") (pinfunction "A_A") (pintype "passive"))
      (node (ref "R1") (pin "1") (pinfunction "1_1") (pintype "passive"))
    )
    (net (code "47") (name "Net-(MCU-PA4)") (class "Default")
      (node (ref "MCU") (pin "10") (pinfunction "PA4_10") (pintype "bidirectional"))
      (node (ref "R29") (pin "2") (pinfunction "2_2") (pintype "passive"))
    )
    (net (code "48") (name "Net-(MCU-PA5)") (class "Default")
      (node (ref "MCU") (pin "11") (pinfunction "PA5_11") (pintype "bidirectional"))
      (node (ref "R26") (pin "3") (pinfunction "1_3") (pintype "passive"))
    )
    (net (code "49") (name "Net-(MCU-PA6)") (class "Default")
      (node (ref "MCU") (pin "12") (pinfunction "PA6_12") (pintype "bidirectional"))
      (node (ref "R26") (pin "2") (pinfunction "1_2") (pintype "passive"))
    )
    (net (code "50") (name "Net-(MCU-PA7)") (class "Default")
      (node (ref "MCU") (pin "13") (pinfunction "PA7_13") (pintype "bidirectional"))
      (node (ref "R26") (pin "1") (pinfunction "1_1") (pintype "passive"))
    )
    (net (code "51") (name "Net-(MCU-PA8)") (class "Default")
      (node (ref "MCU") (pin "14") (pinfunction "PA8_14") (pintype "bidirectional"))
      (node (ref "R25") (pin "4") (pinfunction "1_4") (pintype "passive"))
    )
    (net (code "52") (name "Net-(MCU-PA9)") (class "Default")
      (node (ref "MCU") (pin "15") (pinfunction "PA9_15") (pintype "bidirectional"))
      (node (ref "R25") (pin "3") (pinfunction "1_3") (pintype "passive"))
    )
    (net (code "53") (name "Net-(MCU-PA10)") (class "Default")
      (node (ref "MCU") (pin "16") (pinfunction "PA10_16") (pintype "bidirectional"))
      (node (ref "R25") (pin "2") (pinfunction "1_2") (pintype "passive"))
    )
    (net (code "54") (name "Net-(MCU-PA11)") (class "Default")
      (node (ref "MCU") (pin "17") (pinfunction "PA11_17") (pintype "bidirectional"))
      (node (ref "R25") (pin "1") (pinfunction "1_1") (pintype "passive"))
    )
    (net (code "55") (name "Net-(MCU-PA19)") (class "Default")
      (node (ref "MCU") (pin "25") (pinfunction "PA19_25") (pintype "bidirectional"))
      (node (ref "R26") (pin "4") (pinfunction "1_4") (pintype "passive"))
    )
    (net (code "56") (name "Net-(MCU-PA20)") (class "Default")
      (node (ref "MCU") (pin "28") (pinfunction "PA20_28") (pintype "bidirectional"))
      (node (ref "R27") (pin "4") (pinfunction "1_4") (pintype "passive"))
    )
    (net (code "57") (name "Net-(MCU-PA21)") (class "Default")
      (node (ref "MCU") (pin "29") (pinfunction "PA21_29") (pintype "bidirectional"))
      (node (ref "R27") (pin "3") (pinfunction "1_3") (pintype "passive"))
    )
    (net (code "58") (name "Net-(MCU-PA22)") (class "Default")
      (node (ref "MCU") (pin "30") (pinfunction "PA22_30") (pintype "bidirectional"))
      (node (ref "R27") (pin "2") (pinfunction "1_2") (pintype "passive"))
    )
    (net (code "59") (name "Net-(MCU-PA23)") (class "Default")
      (node (ref "MCU") (pin "31") (pinfunction "PA23_31") (pintype "bidirectional"))
      (node (ref "R27") (pin "1") (pinfunction "1_1") (pintype "passive"))
    )
    (net (code "60") (name "Net-(MCU-PA24)") (class "Default")
      (node (ref "MCU") (pin "32") (pinfunction "PA24_32") (pintype "bidirectional"))
      (node (ref "R28") (pin "4") (pinfunction "1_4") (pintype "passive"))
    )
    (net (code "61") (name "Net-(MCU-PA25)") (class "Default")
      (node (ref "MCU") (pin "33") (pinfunction "PA25_33") (pintype "bidirectional"))
      (node (ref "R28") (pin "3") (pinfunction "1_3") (pintype "passive"))
    )
    (net (code "62") (name "Net-(MCU-PC7)") (class "Default")
      (node (ref "MCU") (pin "58") (pinfunction "PC7_58") (pintype "bidirectional"))
      (node (ref "U$2") (pin "8") (pinfunction "P$1_8") (pintype "bidirectional"))
    )
    (net (code "63") (name "Net-(MCU-PC11)") (class "Default")
      (node (ref "MCU") (pin "59") (pinfunction "PC11_59") (pintype "bidirectional"))
      (node (ref "U$3") (pin "3") (pinfunction "P$1_3") (pintype "bidirectional"))
    )
    (net (code "64") (name "Net-(MCU-PC12)") (class "Default")
      (node (ref "MCU") (pin "60") (pinfunction "PC12_60") (pintype "bidirectional"))
      (node (ref "U$2") (pin "7") (pinfunction "P$1_7") (pintype "bidirectional"))
    )
    (net (code "65") (name "Net-(MCU-PC13)") (class "Default")
      (node (ref "MCU") (pin "61") (pinfunction "PC13_61") (pintype "bidirectional"))
      (node (ref "U$3") (pin "4") (pinfunction "P$1_4") (pintype "bidirectional"))
    )
    (net (code "66") (name "Net-(MCU-PC14)") (class "Default")
      (node (ref "MCU") (pin "62") (pinfunction "PC14_62") (pintype "bidirectional"))
      (node (ref "U$2") (pin "6") (pinfunction "P$1_6") (pintype "bidirectional"))
    )
    (net (code "67") (name "Net-(MCU-PC15)") (class "Default")
      (node (ref "MCU") (pin "63") (pinfunction "PC15_63") (pintype "bidirectional"))
      (node (ref "U$3") (pin "5") (pinfunction "P$1_5") (pintype "bidirectional"))
    )
    (net (code "68") (name "Net-(MCU-PC16)") (class "Default")
      (node (ref "MCU") (pin "64") (pinfunction "PC16_64") (pintype "bidirectional"))
      (node (ref "U$2") (pin "5") (pinfunction "P$1_5") (pintype "bidirectional"))
    )
    (net (code "69") (name "Net-(MCU-PC17)") (class "Default")
      (node (ref "MCU") (pin "65") (pinfunction "PC17_65") (pintype "bidirectional"))
      (node (ref "U$3") (pin "6") (pinfunction "P$1_6") (pintype "bidirectional"))
    )
    (net (code "70") (name "Net-(MCU-PC18)") (class "Default")
      (node (ref "MCU") (pin "66") (pinfunction "PC18_66") (pintype "bidirectional"))
      (node (ref "U$2") (pin "4") (pinfunction "P$1_4") (pintype "bidirectional"))
    )
    (net (code "71") (name "Net-(MCU-PC19)") (class "Default")
      (node (ref "MCU") (pin "67") (pinfunction "PC19_67") (pintype "bidirectional"))
      (node (ref "U$3") (pin "7") (pinfunction "P$1_7") (pintype "bidirectional"))
    )
    (net (code "72") (name "Net-(MCU-PC20)") (class "Default")
      (node (ref "MCU") (pin "68") (pinfunction "PC20_68") (pintype "bidirectional"))
      (node (ref "U$2") (pin "3") (pinfunction "P$1_3") (pintype "bidirectional"))
    )
    (net (code "73") (name "Net-(MCU-PC21)") (class "Default")
      (node (ref "MCU") (pin "69") (pinfunction "PC21_69") (pintype "bidirectional"))
      (node (ref "U$3") (pin "8") (pinfunction "P$1_8") (pintype "bidirectional"))
    )
    (net (code "74") (name "Net-(MCU-PC22)") (class "Default")
      (node (ref "MCU") (pin "70") (pinfunction "PC22_70") (pintype "bidirectional"))
      (node (ref "U$2") (pin "2") (pinfunction "P$1_2") (pintype "bidirectional"))
    )
    (net (code "75") (name "Net-(MCU-PC23)") (class "Default")
      (node (ref "MCU") (pin "71") (pinfunction "PC23_71") (pintype "bidirectional"))
      (node (ref "U$3") (pin "9") (pinfunction "P$1_9") (pintype "bidirectional"))
    )
    (net (code "76") (name "Net-(MCU-PC24)") (class "Default")
      (node (ref "MCU") (pin "72") (pinfunction "PC24_72") (pintype "bidirectional"))
      (node (ref "U$2") (pin "1") (pinfunction "P$1_1") (pintype "bidirectional"))
    )
    (net (code "77") (name "Net-(MCU-PC31)") (class "Default")
      (node (ref "MCU") (pin "73") (pinfunction "PC31_73") (pintype "bidirectional"))
      (node (ref "U$3") (pin "10") (pinfunction "P$1_10") (pintype "bidirectional"))
    )
    (net (code "78") (name "Net-(MCU-VDDCORE)") (class "Default")
      (node (ref "C16") (pin "1") (pinfunction "1_1") (pintype "passive"))
      (node (ref "C8") (pin "1") (pinfunction "1_1") (pintype "passive"))
      (node (ref "C9") (pin "1") (pinfunction "1_1") (pintype "passive"))
      (node (ref "MCU") (pin "40") (pinfunction "VDDCORE_40") (pintype "bidirectional"))
    )
    (net (code "79") (name "Net-(MCU-VDD_33)") (class "Default")
      (node (ref "C14") (pin "1") (pinfunction "1_1") (pintype "passive"))
      (node (ref "C6") (pin "1") (pinfunction "1_1") (pintype "passive"))
      (node (ref "C7") (pin "1") (pinfunction "1_1") (pintype "passive"))
      (node (ref "MCU") (pin "39") (pinfunction "VDD_33_39") (pintype "bidirectional"))
    )
    (net (code "80") (name "Net-(R7A-2)") (class "Default")
      (node (ref "LERROR") (pin "A") (pinfunction "A_A") (pintype "passive"))
      (node (ref "R7") (pin "8") (pinfunction "2_8") (pintype "passive"))
    )
    (net (code "81") (name "Net-(R7B-1)") (class "Default")
      (node (ref "4-NMOS1") (pin "14") (pinfunction "14_14") (pintype "passive"))
      (node (ref "R7") (pin "2") (pinfunction "1_2") (pintype "passive"))
    )
    (net (code "82") (name "Net-(R7B-2)") (class "Default")
      (node (ref "LSTOP") (pin "A") (pinfunction "A_A") (pintype "passive"))
      (node (ref "R7") (pin "7") (pinfunction "2_7") (pintype "passive"))
    )
    (net (code "83") (name "Net-(R7C-1)") (class "Default")
      (node (ref "4-NMOS1") (pin "5") (pinfunction "5_5") (pintype "passive"))
      (node (ref "R7") (pin "4") (pinfunction "1_4") (pintype "passive"))
    )
    (net (code "84") (name "Net-(R7C-2)") (class "Default")
      (node (ref "LSTART") (pin "A") (pinfunction "A_A") (pintype "passive"))
      (node (ref "R7") (pin "5") (pinfunction "2_5") (pintype "passive"))
    )
    (net (code "85") (name "Net-(R7D-1)") (class "Default")
      (node (ref "4-NMOS1") (pin "1") (pinfunction "1_1") (pintype "passive"))
      (node (ref "R7") (pin "3") (pinfunction "1_3") (pintype "passive"))
    )
    (net (code "86") (name "Net-(R7D-2)") (class "Default")
      (node (ref "LRUN") (pin "A") (pinfunction "A_A") (pintype "passive"))
      (node (ref "R7") (pin "6") (pinfunction "2_6") (pintype "passive"))
    )
    (net (code "87") (name "Net-(R30B-1)") (class "Default")
      (node (ref "4-NMOS") (pin "14") (pinfunction "14_14") (pintype "passive"))
      (node (ref "R30") (pin "2") (pinfunction "1_2") (pintype "passive"))
    )
    (net (code "88") (name "Net-(R30C-1)") (class "Default")
      (node (ref "4-NMOS") (pin "5") (pinfunction "5_5") (pintype "passive"))
      (node (ref "R30") (pin "4") (pinfunction "1_4") (pintype "passive"))
    )
    (net (code "89") (name "Net-(R30D-1)") (class "Default")
      (node (ref "4-NMOS") (pin "1") (pinfunction "1_1") (pintype "passive"))
      (node (ref "R30") (pin "3") (pinfunction "1_3") (pintype "passive"))
    )
    (net (code "90") (name "OP0-12_1") (class "Default")
      (node (ref "MCU") (pin "95") (pinfunction "PD30_95") (pintype "bidirectional"))
      (node (ref "OUTPUT_0") (pin "1") (pinfunction "S_1") (pintype "passive"))
    )
    (net (code "91") (name "OP0-12_2") (class "Default")
      (node (ref "MCU") (pin "94") (pinfunction "PD29_94") (pintype "bidirectional"))
      (node (ref "OUTPUT_0") (pin "2") (pinfunction "S_2") (pintype "passive"))
    )
    (net (code "92") (name "OP0-12_3") (class "Default")
      (node (ref "MCU") (pin "93") (pinfunction "PD28_93") (pintype "bidirectional"))
      (node (ref "OUTPUT_0") (pin "3") (pinfunction "S_3") (pintype "passive"))
    )
    (net (code "93") (name "OP0-12_4") (class "Default")
      (node (ref "MCU") (pin "92") (pinfunction "PD27_92") (pintype "bidirectional"))
      (node (ref "OUTPUT_0") (pin "4") (pinfunction "S_4") (pintype "passive"))
    )
    (net (code "94") (name "OP0-24_12") (class "Default")
      (node (ref "MCU") (pin "91") (pinfunction "PD24_91") (pintype "bidirectional"))
      (node (ref "OUTPUT_0") (pin "5") (pinfunction "S_5") (pintype "passive"))
    )
    (net (code "95") (name "OP0-FAN_IN") (class "Default")
      (node (ref "MCU") (pin "90") (pinfunction "PD23_90") (pintype "bidirectional"))
      (node (ref "OUTPUT_0") (pin "6") (pinfunction "S_6") (pintype "passive"))
    )
    (net (code "96") (name "OP0-FAN_TAC") (class "Default")
      (node (ref "MCU") (pin "88") (pinfunction "PD21_88") (pintype "bidirectional"))
      (node (ref "OUTPUT_0") (pin "8") (pinfunction "S_8") (pintype "passive"))
    )
    (net (code "97") (name "OP0-H2_OK1") (class "Default")
      (node (ref "MCU") (pin "86") (pinfunction "PD13_86") (pintype "bidirectional"))
      (node (ref "OUTPUT_0") (pin "10") (pinfunction "S_10") (pintype "passive"))
    )
    (net (code "98") (name "OP0-H2_OK2") (class "Default")
      (node (ref "MCU") (pin "87") (pinfunction "PD14_87") (pintype "bidirectional"))
      (node (ref "OUTPUT_0") (pin "9") (pinfunction "S_9") (pintype "passive"))
      (node (ref "R2") (pin "2") (pinfunction "2_2") (pintype "passive"))
    )
    (net (code "99") (name "OP0-SRV_IN") (class "Default")
      (node (ref "MCU") (pin "89") (pinfunction "PD22_89") (pintype "bidirectional"))
      (node (ref "OUTPUT_0") (pin "7") (pinfunction "S_7") (pintype "passive"))
    )
    (net (code "100") (name "OP1-12_1") (class "Default")
      (node (ref "MCU") (pin "85") (pinfunction "PD12_85") (pintype "bidirectional"))
      (node (ref "OUTPUT_1") (pin "1") (pinfunction "S_1") (pintype "passive"))
    )
    (net (code "101") (name "OP1-12_2") (class "Default")
      (node (ref "MCU") (pin "84") (pinfunction "PD11_84") (pintype "bidirectional"))
      (node (ref "OUTPUT_1") (pin "2") (pinfunction "S_2") (pintype "passive"))
    )
    (net (code "102") (name "OP1-12_3") (class "Default")
      (node (ref "MCU") (pin "81") (pinfunction "PD10_81") (pintype "bidirectional"))
      (node (ref "OUTPUT_1") (pin "3") (pinfunction "S_3") (pintype "passive"))
    )
    (net (code "103") (name "OP1-12_4") (class "Default")
      (node (ref "MCU") (pin "80") (pinfunction "PD9_80") (pintype "bidirectional"))
      (node (ref "OUTPUT_1") (pin "4") (pinfunction "S_4") (pintype "passive"))
    )
    (net (code "104") (name "OP1-24_12") (class "Default")
      (node (ref "MCU") (pin "79") (pinfunction "PD8_79") (pintype "bidirectional"))
      (node (ref "OUTPUT_1") (pin "5") (pinfunction "S_5") (pintype "passive"))
    )
    (net (code "105") (name "OP1-FAN_IN") (class "Default")
      (node (ref "MCU") (pin "78") (pinfunction "PD7_78") (pintype "bidirectional"))
      (node (ref "OUTPUT_1") (pin "6") (pinfunction "S_6") (pintype "passive"))
    )
    (net (code "106") (name "OP1-FAN_TAC") (class "Default")
      (node (ref "MCU") (pin "76") (pinfunction "PD2_76") (pintype "bidirectional"))
      (node (ref "OUTPUT_1") (pin "8") (pinfunction "S_8") (pintype "passive"))
    )
    (net (code "107") (name "OP1-H2_OK1") (class "Default")
      (node (ref "MCU") (pin "74") (pinfunction "PD0_74") (pintype "bidirectional"))
      (node (ref "OUTPUT_1") (pin "10") (pinfunction "S_10") (pintype "passive"))
      (node (ref "R4") (pin "2") (pinfunction "2_2") (pintype "passive"))
    )
    (net (code "108") (name "OP1-H2_OK2") (class "Default")
      (node (ref "MCU") (pin "75") (pinfunction "PD1_75") (pintype "bidirectional"))
      (node (ref "OUTPUT_1") (pin "9") (pinfunction "S_9") (pintype "passive"))
    )
    (net (code "109") (name "OP1-SRV_IN") (class "Default")
      (node (ref "MCU") (pin "77") (pinfunction "PD3_77") (pintype "bidirectional"))
      (node (ref "OUTPUT_1") (pin "7") (pinfunction "S_7") (pintype "passive"))
    )
    (net (code "110") (name "RESCON(S)") (class "Default")
      (node (ref "R19") (pin "1") (pinfunction "1_1") (pintype "passive"))
      (node (ref "RESCON") (pin "P$1") (pinfunction "P$2_P$1") (pintype "bidirectional"))
    )
    (net (code "111") (name "START(S)") (class "Default")
      (node (ref "R20") (pin "1") (pinfunction "1_1") (pintype "passive"))
      (node (ref "START") (pin "P$1") (pinfunction "P$2_P$1") (pintype "bidirectional"))
    )
    (net (code "112") (name "TANKPRES_S+") (class "Default")
      (node (ref "R21") (pin "2") (pinfunction "2_2") (pintype "passive"))
      (node (ref "R26") (pin "6") (pinfunction "2_6") (pintype "passive"))
      (node (ref "TANKPRES") (pin "2") (pinfunction "2_2") (pintype "passive"))
    )
    (net (code "113") (name "TANKPRES_S-") (class "Default")
      (node (ref "R21") (pin "1") (pinfunction "1_1") (pintype "passive"))
      (node (ref "R29") (pin "1") (pinfunction "1_1") (pintype "passive"))
      (node (ref "TANKPRES") (pin "3") (pinfunction "3_3") (pintype "passive"))
    )
    (net (code "114") (name "TCK") (class "Default")
      (node (ref "JTAG") (pin "1") (pinfunction "1_1") (pintype "passive"))
      (node (ref "MCU") (pin "1") (pinfunction "PA0_1") (pintype "bidirectional"))
    )
    (net (code "115") (name "TDI") (class "Default")
      (node (ref "JTAG") (pin "9") (pinfunction "9_9") (pintype "passive"))
      (node (ref "MCU") (pin "2") (pinfunction "PA1_2") (pintype "bidirectional"))
    )
    (net (code "116") (name "TDO") (class "Default")
      (node (ref "JTAG") (pin "3") (pinfunction "3_3") (pintype "passive"))
      (node (ref "MCU") (pin "3") (pinfunction "PA2_3") (pintype "bidirectional"))
    )
    (net (code "117") (name "TMS") (class "Default")
      (node (ref "JTAG") (pin "5") (pinfunction "5_5") (pintype "passive"))
      (node (ref "MCU") (pin "4") (pinfunction "PA3_4") (pintype "bidirectional"))
    )
    (net (code "118") (name "USB_D+") (class "Default")
      (node (ref "JP2") (pin "D+") (pinfunction "D+_D+") (pintype "bidirectional"))
      (node (ref "MCU") (pin "36") (pinfunction "DP_36") (pintype "bidirectional"))
    )
    (net (code "119") (name "USB_D-") (class "Default")
      (node (ref "JP2") (pin "D-") (pinfunction "D-_D-") (pintype "bidirectional"))
      (node (ref "MCU") (pin "35") (pinfunction "DM_35") (pintype "bidirectional"))
    )
    (net (code "120") (name "USB_VBUS") (class "Default")
      (node (ref "JP2") (pin "VBUS") (pinfunction "VBUS_VBUS") (pintype "bidirectional"))
      (node (ref "MCU") (pin "34") (pinfunction "VBUS_34") (pintype "bidirectional"))
    )
    (net (code "121") (name "VCC") (class "Default")
      (node (ref "4-NMOS") (pin "11") (pinfunction "11_11") (pintype "passive"))
      (node (ref "4-NMOS1") (pin "11") (pinfunction "11_11") (pintype "passive"))
      (node (ref "C1") (pin "1") (pinfunction "1_1") (pintype "passive"))
      (node (ref "C11") (pin "+") (pinfunction "+_+") (pintype "passive"))
      (node (ref "C13") (pin "1") (pinfunction "1_1") (pintype "passive"))
      (node (ref "C15") (pin "+") (pinfunction "+_+") (pintype "passive"))
      (node (ref "C17") (pin "1") (pinfunction "1_1") (pintype "passive"))
      (node (ref "C18") (pin "1") (pinfunction "1_1") (pintype "passive"))
      (node (ref "C4") (pin "1") (pinfunction "1_1") (pintype "passive"))
      (node (ref "C5") (pin "1") (pinfunction "1_1") (pintype "passive"))
      (node (ref "CAPCON") (pin "3") (pinfunction "3_3") (pintype "passive"))
      (node (ref "FCCON") (pin "3") (pinfunction "3_3") (pintype "passive"))
      (node (ref "JTAG") (pin "4") (pinfunction "4_4") (pintype "passive"))
      (node (ref "JTAG") (pin "7") (pinfunction "7_7") (pintype "passive"))
      (node (ref "L1") (pin "2") (pinfunction "2_2") (pintype "passive"))
      (node (ref "LD39300") (pin "3") (pinfunction "IN_3") (pintype "input"))
      (node (ref "MCU") (pin "38") (pinfunction "VDD_5_38") (pintype "bidirectional"))
      (node (ref "MCU") (pin "5") (pinfunction "VDDIO1_5") (pintype "bidirectional"))
      (node (ref "MCU") (pin "53") (pinfunction "VDDIO2_53") (pintype "bidirectional"))
      (node (ref "MCU") (pin "82") (pinfunction "VDDIO3_82") (pintype "bidirectional"))
      (node (ref "PWR") (pin "3") (pinfunction "3_3") (pintype "passive"))
      (node (ref "R1") (pin "2") (pinfunction "2_2") (pintype "passive"))
      (node (ref "R10") (pin "1") (pinfunction "1_1") (pintype "passive"))
      (node (ref "R11") (pin "1") (pinfunction "1_1") (pintype "passive"))
      (node (ref "R12") (pin "1") (pinfunction "1_1") (pintype "passive"))
      (node (ref "R13") (pin "1") (pinfunction "1_1") (pintype "passive"))
      (node (ref "R14") (pin "1") (pinfunction "1_1") (pintype "passive"))
      (node (ref "R23") (pin "2") (pinfunction "2_2") (pintype "passive"))
      (node (ref "R45") (pin "2") (pinfunction "2_2") (pintype "passive"))
      (node (ref "R9") (pin "1") (pinfunction "1_1") (pintype "passive"))
      (node (ref "RESCON") (pin "P$2") (pinfunction "P$1_P$2") (pintype "bidirectional"))
      (node (ref "U$2") (pin "9") (pinfunction "P$1_9") (pintype "bidirectional"))
      (node (ref "U$3") (pin "2") (pinfunction "P$1_2") (pintype "bidirectional"))
      (node (ref "U$4") (pin "3") (pinfunction "VDD/5V_3") (pintype "bidirectional"))
      (node (ref "X3") (pin "1") (pinfunction "S_1") (pintype "passive"))
    )
    (net (code "122") (name "unconnected-(MCU-PA12-Pad18)") (class "Default")
      (node (ref "MCU") (pin "18") (pinfunction "PA12_18") (pintype "bidirectional"))
    )
    (net (code "123") (name "unconnected-(MCU-PA13-Pad19)") (class "Default")
      (node (ref "MCU") (pin "19") (pinfunction "PA13_19") (pintype "bidirectional"))
    )
    (net (code "124") (name "unconnected-(MCU-PA14-Pad20)") (class "Default")
      (node (ref "MCU") (pin "20") (pinfunction "PA14_20") (pintype "bidirectional"))
    )
    (net (code "125") (name "unconnected-(MCU-PA15-Pad21)") (class "Default")
      (node (ref "MCU") (pin "21") (pinfunction "PA15_21") (pintype "bidirectional"))
    )
    (net (code "126") (name "unconnected-(MCU-PA16-Pad22)") (class "Default")
      (node (ref "MCU") (pin "22") (pinfunction "PA16_22") (pintype "bidirectional"))
    )
    (net (code "127") (name "unconnected-(MCU-PB2-Pad99)") (class "Default")
      (node (ref "MCU") (pin "99") (pinfunction "PB2_99") (pintype "bidirectional"))
    )
    (net (code "128") (name "unconnected-(MCU-PB3-Pad100)") (class "Default")
      (node (ref "MCU") (pin "100") (pinfunction "PB3_100") (pintype "bidirectional"))
    )
    (net (code "129") (name "unconnected-(MCU-PB6-Pad9)") (class "Default")
      (node (ref "MCU") (pin "9") (pinfunction "PB6_9") (pintype "bidirectional"))
    )
    (net (code "130") (name "unconnected-(MCU-PB22-Pad45)") (class "Default")
      (node (ref "MCU") (pin "45") (pinfunction "PB22_45") (pintype "bidirectional"))
    )
    (net (code "131") (name "unconnected-(MCU-PB23-Pad46)") (class "Default")
      (node (ref "MCU") (pin "46") (pinfunction "PB23_46") (pintype "bidirectional"))
    )
    (net (code "132") (name "unconnected-(MCU-PC0-Pad49)") (class "Default")
      (node (ref "MCU") (pin "49") (pinfunction "PC0_49") (pintype "bidirectional"))
    )
    (net (code "133") (name "unconnected-(MCU-PC4-Pad55)") (class "Default")
      (node (ref "MCU") (pin "55") (pinfunction "PC4_55") (pintype "bidirectional"))
    )
    (net (code "134") (name "unconnected-(MCU-PC5-Pad56)") (class "Default")
      (node (ref "MCU") (pin "56") (pinfunction "PC5_56") (pintype "bidirectional"))
    )
    (net (code "135") (name "unconnected-(MCU-PC6-Pad57)") (class "Default")
      (node (ref "MCU") (pin "57") (pinfunction "PC6_57") (pintype "bidirectional"))
    )
    (net (code "136") (name "unconnected-(U$1A-3-PadB_3)") (class "Default")
      (node (ref "U$1") (pin "B_3") (pinfunction "3_B_3") (pintype "bidirectional"))
    )
    (net (code "137") (name "unconnected-(U$1A-4-PadB_4)") (class "Default")
      (node (ref "U$1") (pin "B_4") (pinfunction "4_B_4") (pintype "bidirectional"))
    )
    (net (code "138") (name "unconnected-(U$1A-5-PadB_5)") (class "Default")
      (node (ref "U$1") (pin "B_5") (pinfunction "5_B_5") (pintype "bidirectional"))
    )
    (net (code "139") (name "unconnected-(U$1A-6-PadB_6)") (class "Default")
      (node (ref "U$1") (pin "B_6") (pinfunction "6_B_6") (pintype "bidirectional"))
    )
    (net (code "140") (name "unconnected-(U$1A-7-PadB_7)") (class "Default")
      (node (ref "U$1") (pin "B_7") (pinfunction "7_B_7") (pintype "bidirectional"))
    )
    (net (code "141") (name "unconnected-(U$1D-3-PadT_3)") (class "Default")
      (node (ref "U$1") (pin "T_3") (pinfunction "3_T_3") (pintype "bidirectional"))
    )
    (net (code "142") (name "unconnected-(U$1D-4-PadT_4)") (class "Default")
      (node (ref "U$1") (pin "T_4") (pinfunction "4_T_4") (pintype "bidirectional"))
    )
    (net (code "143") (name "unconnected-(U$1D-5-PadT_5)") (class "Default")
      (node (ref "U$1") (pin "T_5") (pinfunction "5_T_5") (pintype "bidirectional"))
    )
    (net (code "144") (name "unconnected-(U$1D-6-PadT_6)") (class "Default")
      (node (ref "U$1") (pin "T_6") (pinfunction "6_T_6") (pintype "bidirectional"))
    )
    (net (code "145") (name "unconnected-(U$1D-7-PadT_7)") (class "Default")
      (node (ref "U$1") (pin "T_7") (pinfunction "7_T_7") (pintype "bidirectional"))
    )
    (net (code "146") (name "unconnected-(U$4-VREF-Pad5)") (class "Default")
      (node (ref "U$4") (pin "5") (pinfunction "VREF_5") (pintype "bidirectional"))
    )
  )
)
